# LED.net
KiCad netlist of a schematic drawn in Altium Designer
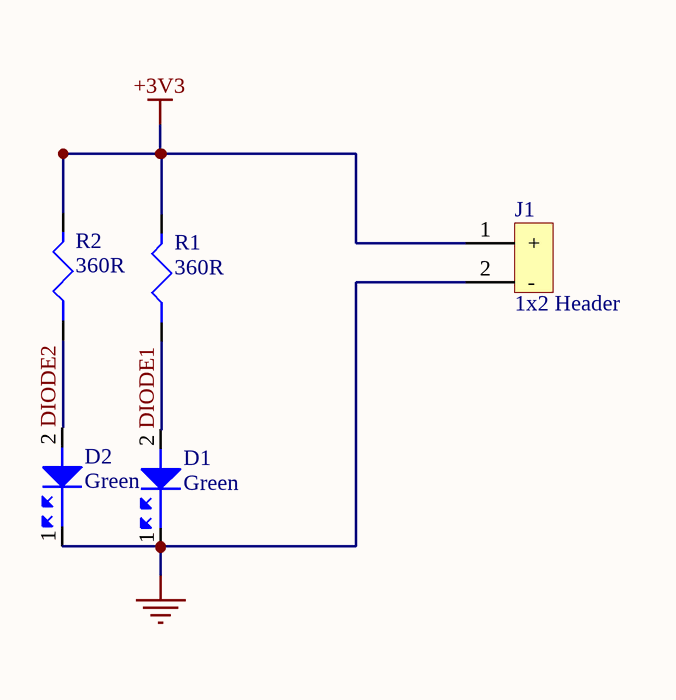
[diagram p0: LED.SchDoc]

(export (version "E")
  (design (tool "Eeschema 10.0.6"))
  (components
    (comp (ref "D1")
      (value "Green")
      (footprint "LED0603G")
      (description "Super Ultra Green 1.6 x 0.8 mm 120° Water Clear 50 mcd 2.2 V Surface Mount LED")
      (fields
        (field (name "MANUFACTURER") "Lumex")
        (field (name "MANUFACTURER PART NUMBER") "SML-LXFM0603SUGCTR")
      )
      (libsource (lib "LED_schlib") (part "SML-LXFM0603SUGCTR"))
    )
    (comp (ref "D2")
      (value "Green")
      (footprint "LED0603G")
      (description "Super Ultra Green 1.6 x 0.8 mm 120° Water Clear 50 mcd 2.2 V Surface Mount LED")
      (fields
        (field (name "MANUFACTURER") "Lumex")
        (field (name "MANUFACTURER PART NUMBER") "SML-LXFM0603SUGCTR")
      )
      (libsource (lib "LED_schlib") (part "SML-LXFM0603SUGCTR"))
    )
    (comp (ref "J1")
      (value "1x2 Header")
      (footprint "HEADER1x2")
      (description "CONN HEADER 2POS .100 VERT TIN")
      (fields (field (name "MANUFACTURER") "Molex") (field (name "MANUFACTURER PART NUMBER") "22-27-2021"))
      (libsource (lib "LED_schlib") (part "22-27-2021"))
    )
    (comp (ref "R1")
      (value "360R")
      (footprint "R0805")
      (description "Res Thick Film 0805 360 Ohm 1% 1/8W ±100ppm/°C Molded SMD SMD Paper T/R")
      (fields
        (field (name "MANUFACTURER") "Vishay")
        (field (name "MANUFACTURER PART NUMBER") "CRCW0805360RFKEA")
      )
      (libsource (lib "LED_schlib") (part "CRCW0805360RFKEA"))
    )
    (comp (ref "R2")
      (value "360R")
      (footprint "R0805")
      (description "Res Thick Film 0805 360 Ohm 1% 1/8W ±100ppm/°C Molded SMD SMD Paper T/R")
      (fields
        (field (name "MANUFACTURER") "Vishay")
        (field (name "MANUFACTURER PART NUMBER") "CRCW0805360RFKEA")
      )
      (libsource (lib "LED_schlib") (part "CRCW0805360RFKEA"))
    )
  )
  (nets
    (net (code "1") (name "+3V3") (class "Default")
      (node (ref "J1") (pin "1") (pinfunction "+_1") (pintype "passive"))
      (node (ref "R1") (pin "2") (pinfunction "2_2") (pintype "passive"))
      (node (ref "R2") (pin "2") (pinfunction "2_2") (pintype "passive"))
    )
    (net (code "2") (name "/DIODE1") (class "Default")
      (node (ref "D1") (pin "2") (pinfunction "2_2") (pintype "passive"))
      (node (ref "R1") (pin "1") (pinfunction "1_1") (pintype "passive"))
    )
    (net (code "3") (name "/DIODE2") (class "Default")
      (node (ref "D2") (pin "2") (pinfunction "2_2") (pintype "passive"))
      (node (ref "R2") (pin "1") (pinfunction "1_1") (pintype "passive"))
    )
    (net (code "4") (name "GND") (class "Default")
      (node (ref "D1") (pin "1") (pinfunction "1_1") (pintype "passive"))
      (node (ref "D2") (pin "1") (pinfunction "1_1") (pintype "passive"))
      (node (ref "J1") (pin "2") (pinfunction "-_2") (pintype "passive"))
    )
  )
)
